# LDOs.net
KiCad netlist of a schematic drawn in Altium Designer
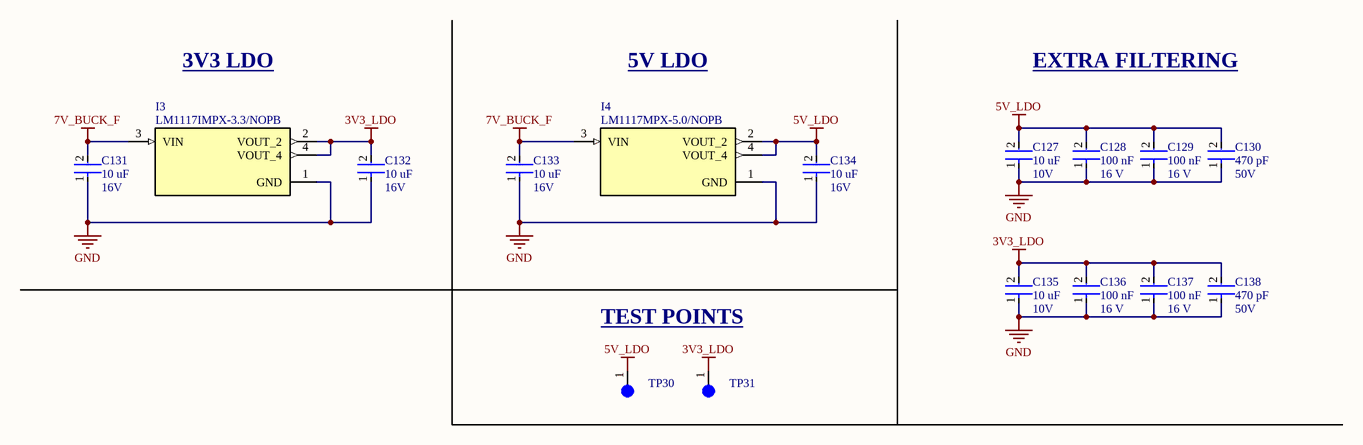
[diagram p0: LDOs.SchDoc]

(export (version "E")
  (design (tool "Eeschema 10.0.6"))
  (components
    (comp (ref "C127")
      (value "CC0603KRX5R6BB106")
      (footprint "CAP-0603")
      (description "CAP CER 10UF 10V X5R 0603")
      (fields (field (name "VOLTAGE") "10V") (field (name "CAPACITANCE") "10 uF"))
      (libsource (lib "JLC_25") (part "CAP-10U-0001"))
    )
    (comp (ref "C128")
      (value "CC0402KRX7R7BB104")
      (footprint "CAP-0402")
      (description "CAP CER 0.1UF 16V X7R 0402")
      (fields (field (name "VOLTAGE RATING") "16 V") (field (name "CAPACITANCE") "100 nF"))
      (libsource (lib "JLC_25") (part "CAP-0.1U-0001"))
    )
    (comp (ref "C129")
      (value "CC0402KRX7R7BB104")
      (footprint "CAP-0402")
      (description "CAP CER 0.1UF 16V X7R 0402")
      (fields (field (name "VOLTAGE RATING") "16 V") (field (name "CAPACITANCE") "100 nF"))
      (libsource (lib "JLC_25") (part "CAP-0.1U-0001"))
    )
    (comp (ref "C130")
      (value "CC0805JRNPO9BN471")
      (footprint "CAP-0805")
      (description "CAP CER 470PF 50V C0G/NPO 0805")
      (fields (field (name "VOLTAGE") "50V") (field (name "CAPACITANCE") "470 pF"))
      (libsource (lib "JLC_25") (part "CAP-470P-0001"))
    )
    (comp (ref "C131")
      (value "293D106X9016A2TE3")
      (footprint "CAP-1210")
      (description "CAP TANT 10UF 10% 16V 1206")
      (fields (field (name "VOLTAGE") "16V") (field (name "CAPACITANCE") "10 uF"))
      (libsource (lib "JLC_25") (part "CAP-10U-0003"))
    )
    (comp (ref "C132")
      (value "293D106X9016A2TE3")
      (footprint "CAP-1210")
      (description "CAP TANT 10UF 10% 16V 1206")
      (fields (field (name "VOLTAGE") "16V") (field (name "CAPACITANCE") "10 uF"))
      (libsource (lib "JLC_25") (part "CAP-10U-0003"))
    )
    (comp (ref "C133")
      (value "293D106X9016A2TE3")
      (footprint "CAP-1210")
      (description "CAP TANT 10UF 10% 16V 1206")
      (fields (field (name "VOLTAGE") "16V") (field (name "CAPACITANCE") "10 uF"))
      (libsource (lib "JLC_25") (part "CAP-10U-0003"))
    )
    (comp (ref "C134")
      (value "293D106X9016A2TE3")
      (footprint "CAP-1210")
      (description "CAP TANT 10UF 10% 16V 1206")
      (fields (field (name "VOLTAGE") "16V") (field (name "CAPACITANCE") "10 uF"))
      (libsource (lib "JLC_25") (part "CAP-10U-0003"))
    )
    (comp (ref "C135")
      (value "CC0603KRX5R6BB106")
      (footprint "CAP-0603")
      (description "CAP CER 10UF 10V X5R 0603")
      (fields (field (name "VOLTAGE") "10V") (field (name "CAPACITANCE") "10 uF"))
      (libsource (lib "JLC_25") (part "CAP-10U-0001"))
    )
    (comp (ref "C136")
      (value "CC0402KRX7R7BB104")
      (footprint "CAP-0402")
      (description "CAP CER 0.1UF 16V X7R 0402")
      (fields (field (name "VOLTAGE RATING") "16 V") (field (name "CAPACITANCE") "100 nF"))
      (libsource (lib "JLC_25") (part "CAP-0.1U-0001"))
    )
    (comp (ref "C137")
      (value "CC0402KRX7R7BB104")
      (footprint "CAP-0402")
      (description "CAP CER 0.1UF 16V X7R 0402")
      (fields (field (name "VOLTAGE RATING") "16 V") (field (name "CAPACITANCE") "100 nF"))
      (libsource (lib "JLC_25") (part "CAP-0.1U-0001"))
    )
    (comp (ref "C138")
      (value "CC0805JRNPO9BN471")
      (footprint "CAP-0805")
      (description "CAP CER 470PF 50V C0G/NPO 0805")
      (fields (field (name "VOLTAGE") "50V") (field (name "CAPACITANCE") "470 pF"))
      (libsource (lib "JLC_25") (part "CAP-470P-0001"))
    )
    (comp (ref "I3")
      (value "LM1117IMPX-3.3/NOPB")
      (footprint "IC-SOT-223-4")
      (description "IC REG LIN 3.3V 800MA SOT223-4")
      (libsource (lib "JLC_25") (part "IC_LDO_3V3_0001"))
    )
    (comp (ref "I4")
      (value "LM1117MPX-5.0/NOPB")
      (footprint "IC-SOT-223-4")
      (description "IC REG LINEAR 5V 800MA SOT223-4")
      (libsource (lib "JLC_25") (part "IC_LDO_5V_0001"))
    )
    (comp (ref "TP30")
      (value "5003")
      (footprint "TEST-POINT-0001")
      (description "Oranange PC Test Point, Miniature Phoisphor Bronze Silver Plating Through Hole Mounting Type")
      (libsource (lib "*") (part "TEST-POINT-0001"))
    )
    (comp (ref "TP31")
      (value "5003")
      (footprint "TEST-POINT-0001")
      (description "Oranange PC Test Point, Miniature Phoisphor Bronze Silver Plating Through Hole Mounting Type")
      (libsource (lib "*") (part "TEST-POINT-0001"))
    )
  )
  (nets
    (net (code "1") (name "3V3_LDO") (class "Default")
      (node (ref "C132") (pin "2") (pinfunction "2_2") (pintype "passive"))
      (node (ref "C135") (pin "2") (pinfunction "2_2") (pintype "passive"))
      (node (ref "C136") (pin "2") (pinfunction "2_2") (pintype "passive"))
      (node (ref "C137") (pin "2") (pinfunction "2_2") (pintype "passive"))
      (node (ref "C138") (pin "2") (pinfunction "2_2") (pintype "passive"))
      (node (ref "I3") (pin "2") (pinfunction "VOUT_2_2") (pintype "output"))
      (node (ref "I3") (pin "4") (pinfunction "VOUT_4_4") (pintype "output"))
      (node (ref "TP31") (pin "1") (pinfunction "0_1") (pintype "passive"))
    )
    (net (code "2") (name "5V_LDO") (class "Default")
      (node (ref "C127") (pin "2") (pinfunction "2_2") (pintype "passive"))
      (node (ref "C128") (pin "2") (pinfunction "2_2") (pintype "passive"))
      (node (ref "C129") (pin "2") (pinfunction "2_2") (pintype "passive"))
      (node (ref "C130") (pin "2") (pinfunction "2_2") (pintype "passive"))
      (node (ref "C134") (pin "2") (pinfunction "2_2") (pintype "passive"))
      (node (ref "I4") (pin "2") (pinfunction "VOUT_2_2") (pintype "output"))
      (node (ref "I4") (pin "4") (pinfunction "VOUT_4_4") (pintype "output"))
      (node (ref "TP30") (pin "1") (pinfunction "0_1") (pintype "passive"))
    )
    (net (code "3") (name "7V_BUCK_F") (class "Default")
      (node (ref "C131") (pin "2") (pinfunction "2_2") (pintype "passive"))
      (node (ref "C133") (pin "2") (pinfunction "2_2") (pintype "passive"))
      (node (ref "I3") (pin "3") (pinfunction "VIN_3") (pintype "input"))
      (node (ref "I4") (pin "3") (pinfunction "VIN_3") (pintype "input"))
    )
    (net (code "4") (name "GND") (class "Default")
      (node (ref "C127") (pin "1") (pinfunction "1_1") (pintype "passive"))
      (node (ref "C128") (pin "1") (pinfunction "1_1") (pintype "passive"))
      (node (ref "C129") (pin "1") (pinfunction "1_1") (pintype "passive"))
      (node (ref "C130") (pin "1") (pinfunction "1_1") (pintype "passive"))
      (node (ref "C131") (pin "1") (pinfunction "1_1") (pintype "passive"))
      (node (ref "C132") (pin "1") (pinfunction "1_1") (pintype "passive"))
      (node (ref "C133") (pin "1") (pinfunction "1_1") (pintype "passive"))
      (node (ref "C134") (pin "1") (pinfunction "1_1") (pintype "passive"))
      (node (ref "C135") (pin "1") (pinfunction "1_1") (pintype "passive"))
      (node (ref "C136") (pin "1") (pinfunction "1_1") (pintype "passive"))
      (node (ref "C137") (pin "1") (pinfunction "1_1") (pintype "passive"))
      (node (ref "C138") (pin "1") (pinfunction "1_1") (pintype "passive"))
      (node (ref "I3") (pin "1") (pinfunction "GND_1") (pintype "power_in"))
      (node (ref "I4") (pin "1") (pinfunction "GND_1") (pintype "power_in"))
    )
  )
)
